# Elkapod_power_supply.net
KiCad netlist of a schematic drawn in Altium Designer
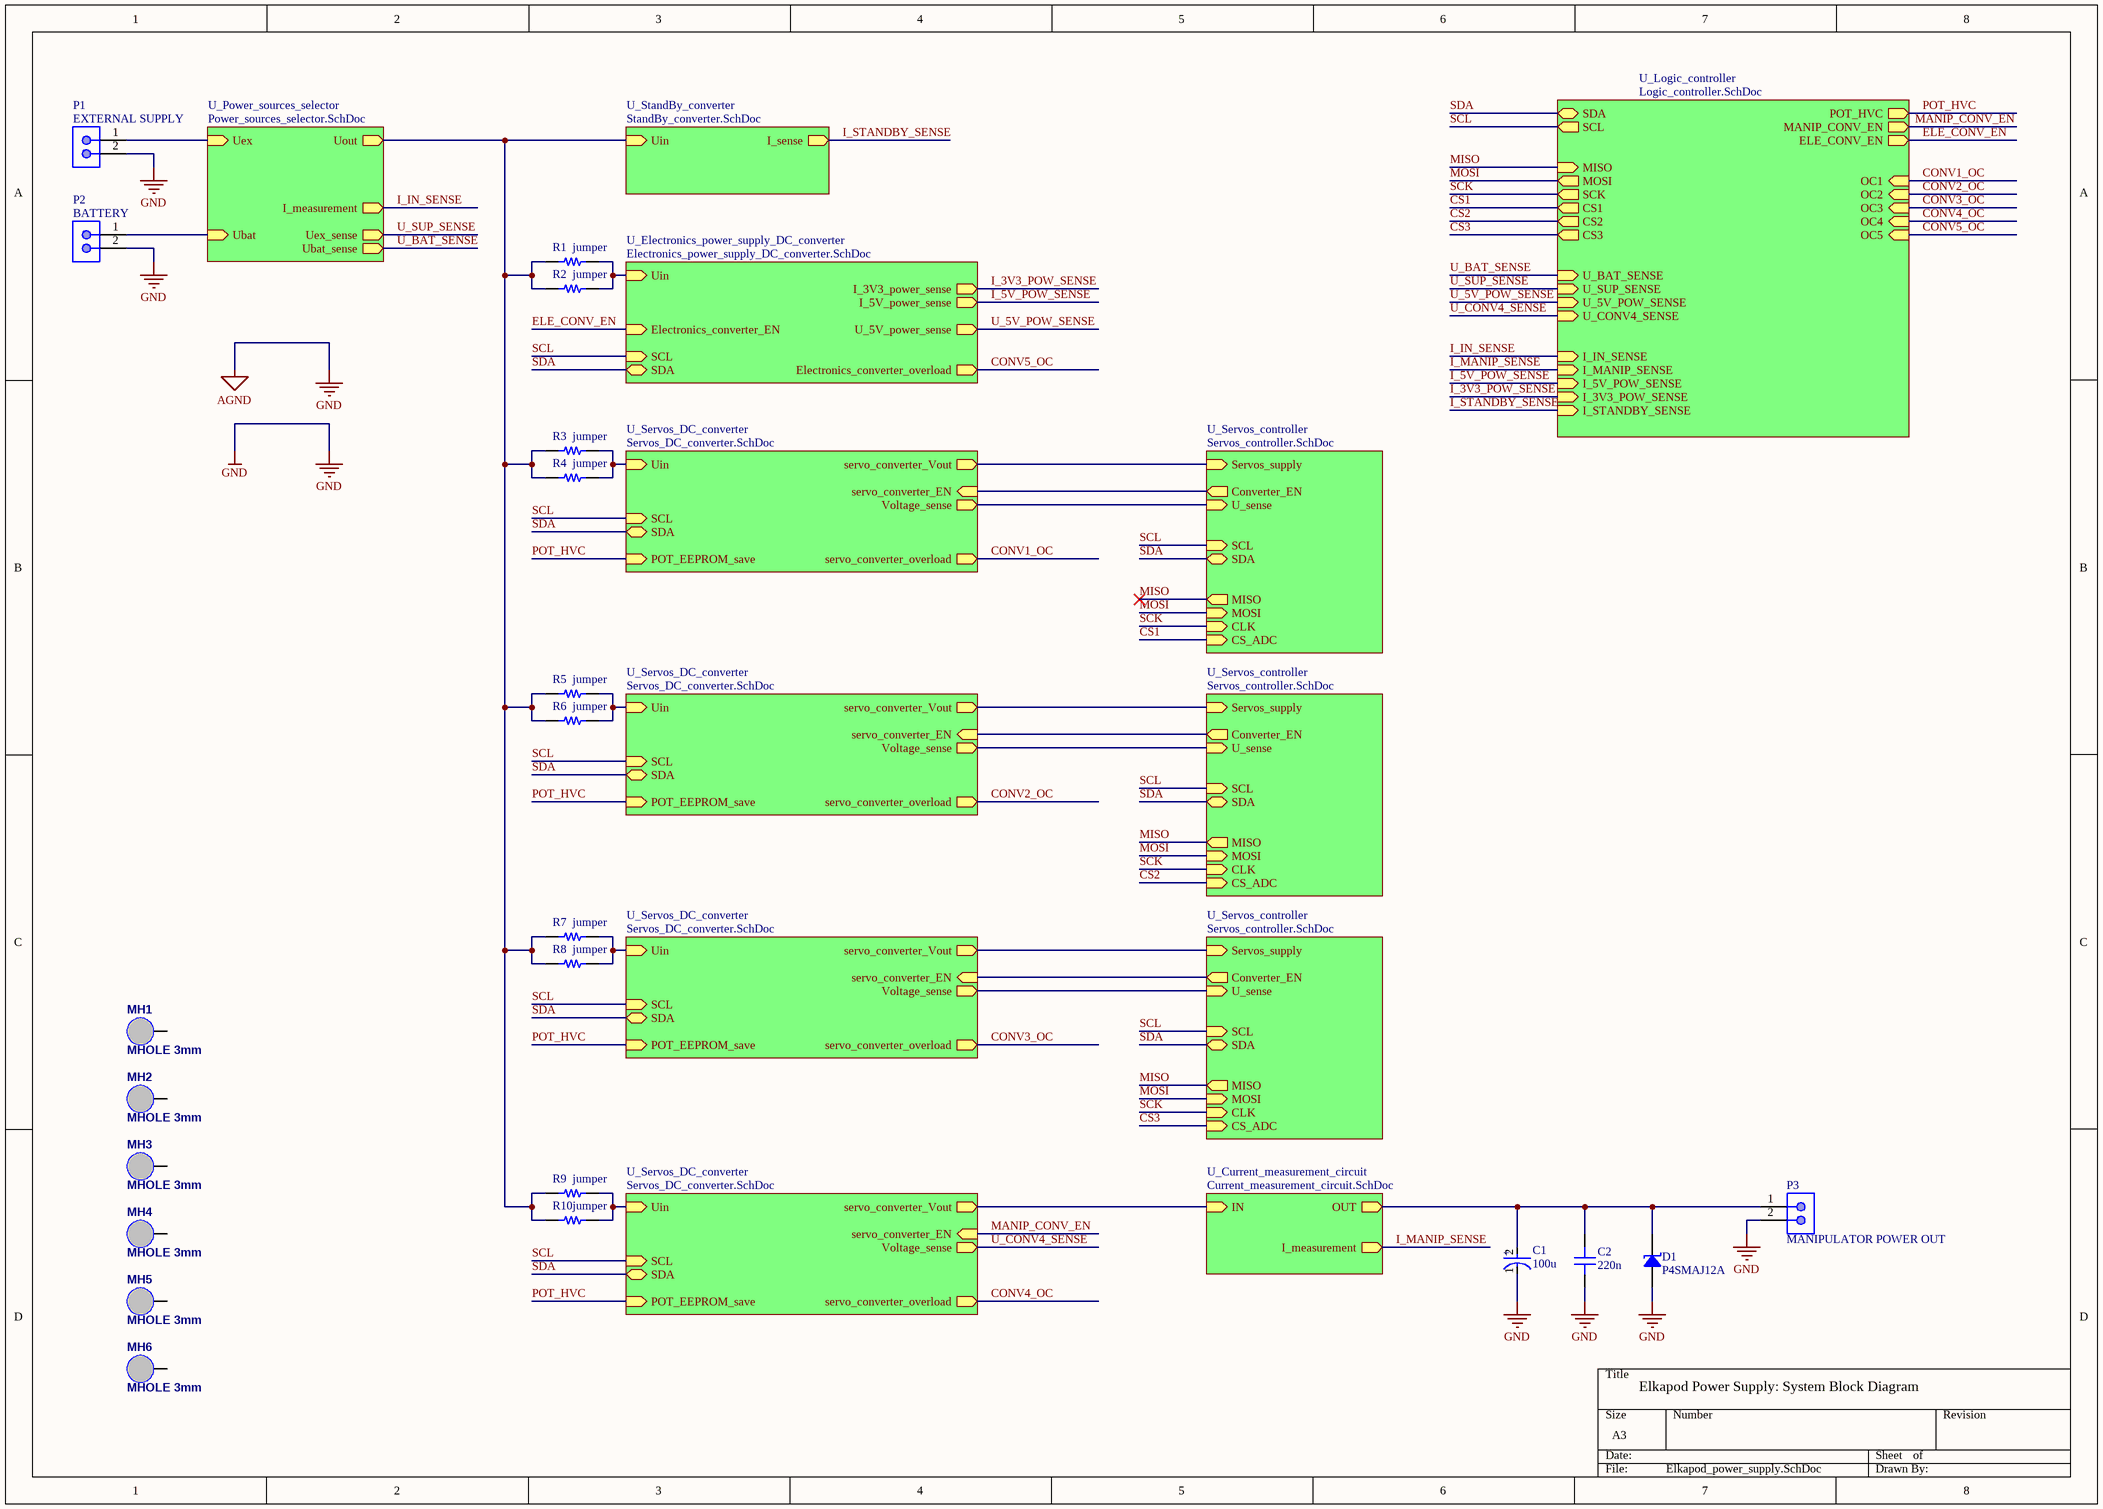
[diagram p0: Elkapod_power_supply.SchDoc]

(export (version "E")
  (design (tool "Eeschema 10.0.6"))
  (components
    (comp (ref "C1")
      (value "100u")
      (footprint "FP-FKE-MFG")
      (description "CAP ALUM 100UF 20% 25V SMD")
      (fields (field (name "TOLERANCE") "20%") (field (name "VOLTAGE") "25V"))
      (libsource (lib "Altium Content Vault") (part "203bc49f2ac43e59fd269a8c329ed05"))
    )
    (comp (ref "C2")
      (value "220n")
      (footprint "CAP 0603_1608")
      (description "CAP CER 220nF 25V X5R 0603")
      (fields (field (name "PART NUMBER") "C0603C272F3GAC7867") (field (name "MANUFACTURER") "KEMET"))
      (libsource (lib "Celestial Altium Library - altium_library") (part "Capacitor"))
    )
    (comp (ref "D1")
      (value "P4SMAJ12A")
      (footprint "DO214AC SMA")
      (description "TVS DIODE 12VDC DO214AC")
      (fields (field (name "PART NUMBER") "P4SMAJ9.0A"))
      (libsource (lib "Celestial Altium Library - altium_library") (part "DIODE TVS UNI"))
    )
    (comp (ref "MH1")
      (value "MHOLE 3mm")
      (footprint "3mm screw drill III")
      (description "3mm Mounting Hole")
      (libsource (lib "mechanical_other") (part "MHOLE_3MM"))
    )
    (comp (ref "MH2")
      (value "MHOLE 3mm")
      (footprint "3mm screw drill III")
      (description "3mm Mounting Hole")
      (libsource (lib "mechanical_other") (part "MHOLE_3MM"))
    )
    (comp (ref "MH3")
      (value "MHOLE 3mm")
      (footprint "3mm screw drill III")
      (description "3mm Mounting Hole")
      (libsource (lib "mechanical_other") (part "MHOLE_3MM"))
    )
    (comp (ref "MH4")
      (value "MHOLE 3mm")
      (footprint "3mm screw drill III")
      (description "3mm Mounting Hole")
      (libsource (lib "mechanical_other") (part "MHOLE_3MM"))
    )
    (comp (ref "MH5")
      (value "MHOLE 3mm")
      (footprint "3mm screw drill III")
      (description "3mm Mounting Hole")
      (libsource (lib "mechanical_other") (part "MHOLE_3MM"))
    )
    (comp (ref "MH6")
      (value "MHOLE 3mm")
      (footprint "3mm screw drill III")
      (description "3mm Mounting Hole")
      (libsource (lib "mechanical_other") (part "MHOLE_3MM"))
    )
    (comp (ref "P1")
      (value "EXTERNAL SUPPLY")
      (footprint "XT60PW-M")
      (description "XT60PW-M; 30A/500V angled female DC PCB socket (pin1 -> +, pin2 -> -)")
      (libsource (lib "My_sockets") (part "XT60PW-M"))
    )
    (comp (ref "P2")
      (value "BATTERY")
      (footprint "XT60PW-M")
      (description "XT60PW-M; 30A/500V angled female DC PCB socket (pin1 -> +, pin2 -> -)")
      (libsource (lib "My_sockets") (part "XT60PW-M"))
    )
    (comp (ref "P3")
      (value "MANIPULATOR POWER OUT")
      (footprint "XT60PW-M")
      (description "XT60PW-M; 30A/500V angled female DC PCB socket (pin1 -> +, pin2 -> -)")
      (libsource (lib "") (part "XT60PW-M_1"))
    )
    (comp (ref "R1")
      (value "jumper")
      (footprint "STACKPOLE CSM2512")
      (description "RES 0 OHM 1W 2512")
      (fields
        (field (name "PART NUMBER") "CSM2512FT20L0")
        (field (name "MANUFACTURER") "Stackpole Electronics Inc")
      )
      (libsource (lib "Celestial Altium Library - altium_library") (part "Resistor"))
    )
    (comp (ref "R2")
      (value "jumper")
      (footprint "STACKPOLE CSM2512")
      (description "RES 0 OHM 1W 2512")
      (fields
        (field (name "PART NUMBER") "CSM2512FT20L0")
        (field (name "MANUFACTURER") "Stackpole Electronics Inc")
      )
      (libsource (lib "Celestial Altium Library - altium_library") (part "Resistor"))
    )
    (comp (ref "R3")
      (value "jumper")
      (footprint "STACKPOLE CSM2512")
      (description "RES 0 OHM 1W 2512")
      (fields
        (field (name "PART NUMBER") "CSM2512FT20L0")
        (field (name "MANUFACTURER") "Stackpole Electronics Inc")
      )
      (libsource (lib "Celestial Altium Library - altium_library") (part "Resistor"))
    )
    (comp (ref "R4")
      (value "jumper")
      (footprint "STACKPOLE CSM2512")
      (description "RES 0 OHM 1W 2512")
      (fields
        (field (name "PART NUMBER") "CSM2512FT20L0")
        (field (name "MANUFACTURER") "Stackpole Electronics Inc")
      )
      (libsource (lib "Celestial Altium Library - altium_library") (part "Resistor"))
    )
    (comp (ref "R5")
      (value "jumper")
      (footprint "STACKPOLE CSM2512")
      (description "RES 0 OHM 1W 2512")
      (fields
        (field (name "PART NUMBER") "CSM2512FT20L0")
        (field (name "MANUFACTURER") "Stackpole Electronics Inc")
      )
      (libsource (lib "Celestial Altium Library - altium_library") (part "Resistor"))
    )
    (comp (ref "R6")
      (value "jumper")
      (footprint "STACKPOLE CSM2512")
      (description "RES 0 OHM 1W 2512")
      (fields
        (field (name "PART NUMBER") "CSM2512FT20L0")
        (field (name "MANUFACTURER") "Stackpole Electronics Inc")
      )
      (libsource (lib "Celestial Altium Library - altium_library") (part "Resistor"))
    )
    (comp (ref "R7")
      (value "jumper")
      (footprint "STACKPOLE CSM2512")
      (description "RES 0 OHM 1W 2512")
      (fields
        (field (name "PART NUMBER") "CSM2512FT20L0")
        (field (name "MANUFACTURER") "Stackpole Electronics Inc")
      )
      (libsource (lib "Celestial Altium Library - altium_library") (part "Resistor"))
    )
    (comp (ref "R8")
      (value "jumper")
      (footprint "STACKPOLE CSM2512")
      (description "RES 0 OHM 1W 2512")
      (fields
        (field (name "PART NUMBER") "CSM2512FT20L0")
        (field (name "MANUFACTURER") "Stackpole Electronics Inc")
      )
      (libsource (lib "Celestial Altium Library - altium_library") (part "Resistor"))
    )
    (comp (ref "R9")
      (value "jumper")
      (footprint "STACKPOLE CSM2512")
      (description "RES 0 OHM 1W 2512")
      (fields
        (field (name "PART NUMBER") "CSM2512FT20L0")
        (field (name "MANUFACTURER") "Stackpole Electronics Inc")
      )
      (libsource (lib "Celestial Altium Library - altium_library") (part "Resistor"))
    )
    (comp (ref "R10")
      (value "jumper")
      (footprint "STACKPOLE CSM2512")
      (description "RES 0 OHM 1W 2512")
      (fields
        (field (name "PART NUMBER") "CSM2512FT20L0")
        (field (name "MANUFACTURER") "Stackpole Electronics Inc")
      )
      (libsource (lib "Celestial Altium Library - altium_library") (part "Resistor"))
    )
  )
  (nets
    (net (code "21") (name "/OUT") (class "Default")
      (node (ref "C1") (pin "2") (pinfunction "A_2") (pintype "passive"))
      (node (ref "C2") (pin "1") (pinfunction "1_1") (pintype "passive"))
      (node (ref "D1") (pin "2") (pinfunction "2_2") (pintype "passive"))
      (node (ref "P3") (pin "1") (pinfunction "+_1") (pintype "passive"))
    )
    (net (code "30") (name "/Ubat") (class "Default")
      (node (ref "P2") (pin "1") (pinfunction "+_1") (pintype "passive"))
    )
    (net (code "31") (name "/Uex") (class "Default")
      (node (ref "P1") (pin "1") (pinfunction "+_1") (pintype "passive"))
    )
    (net (code "32") (name "/Uin") (class "Default")
      (node (ref "R1") (pin "1") (pinfunction "1_1") (pintype "passive"))
      (node (ref "R2") (pin "1") (pinfunction "1_1") (pintype "passive"))
    )
    (net (code "33") (name "/Uin_1") (class "Default")
      (node (ref "R5") (pin "1") (pinfunction "1_1") (pintype "passive"))
      (node (ref "R6") (pin "1") (pinfunction "1_1") (pintype "passive"))
    )
    (net (code "34") (name "/Uin_2") (class "Default")
      (node (ref "R7") (pin "1") (pinfunction "1_1") (pintype "passive"))
      (node (ref "R8") (pin "1") (pinfunction "1_1") (pintype "passive"))
    )
    (net (code "35") (name "/Uin_3") (class "Default")
      (node (ref "R3") (pin "1") (pinfunction "1_1") (pintype "passive"))
      (node (ref "R4") (pin "1") (pinfunction "1_1") (pintype "passive"))
    )
    (net (code "36") (name "/Uin_4") (class "Default")
      (node (ref "R10") (pin "1") (pinfunction "1_1") (pintype "passive"))
      (node (ref "R9") (pin "1") (pinfunction "1_1") (pintype "passive"))
    )
    (net (code "37") (name "/Uout") (class "Default")
      (node (ref "R1") (pin "2") (pinfunction "2_2") (pintype "passive"))
      (node (ref "R10") (pin "2") (pinfunction "2_2") (pintype "passive"))
      (node (ref "R2") (pin "2") (pinfunction "2_2") (pintype "passive"))
      (node (ref "R3") (pin "2") (pinfunction "2_2") (pintype "passive"))
      (node (ref "R4") (pin "2") (pinfunction "2_2") (pintype "passive"))
      (node (ref "R5") (pin "2") (pinfunction "2_2") (pintype "passive"))
      (node (ref "R6") (pin "2") (pinfunction "2_2") (pintype "passive"))
      (node (ref "R7") (pin "2") (pinfunction "2_2") (pintype "passive"))
      (node (ref "R8") (pin "2") (pinfunction "2_2") (pintype "passive"))
      (node (ref "R9") (pin "2") (pinfunction "2_2") (pintype "passive"))
    )
    (net (code "45") (name "AGND") (class "Default")
      (node (ref "C1") (pin "1") (pinfunction "C_1") (pintype "passive"))
      (node (ref "C2") (pin "2") (pinfunction "2_2") (pintype "passive"))
      (node (ref "D1") (pin "1") (pinfunction "1_1") (pintype "passive"))
      (node (ref "P1") (pin "2") (pinfunction "-_2") (pintype "passive"))
      (node (ref "P2") (pin "2") (pinfunction "-_2") (pintype "passive"))
      (node (ref "P3") (pin "2") (pinfunction "-_2") (pintype "passive"))
    )
    (net (code "46") (name "unconnected-(MH1-GND-Pad1)") (class "Default")
      (node (ref "MH1") (pin "1") (pinfunction "GND_1") (pintype "passive"))
    )
    (net (code "47") (name "unconnected-(MH2-GND-Pad1)") (class "Default")
      (node (ref "MH2") (pin "1") (pinfunction "GND_1") (pintype "passive"))
    )
    (net (code "48") (name "unconnected-(MH3-GND-Pad1)") (class "Default")
      (node (ref "MH3") (pin "1") (pinfunction "GND_1") (pintype "passive"))
    )
    (net (code "49") (name "unconnected-(MH4-GND-Pad1)") (class "Default")
      (node (ref "MH4") (pin "1") (pinfunction "GND_1") (pintype "passive"))
    )
    (net (code "50") (name "unconnected-(MH5-GND-Pad1)") (class "Default")
      (node (ref "MH5") (pin "1") (pinfunction "GND_1") (pintype "passive"))
    )
    (net (code "51") (name "unconnected-(MH6-GND-Pad1)") (class "Default")
      (node (ref "MH6") (pin "1") (pinfunction "GND_1") (pintype "passive"))
    )
  )
)
